# linSen.net
KiCad netlist of a schematic drawn in EAGLE
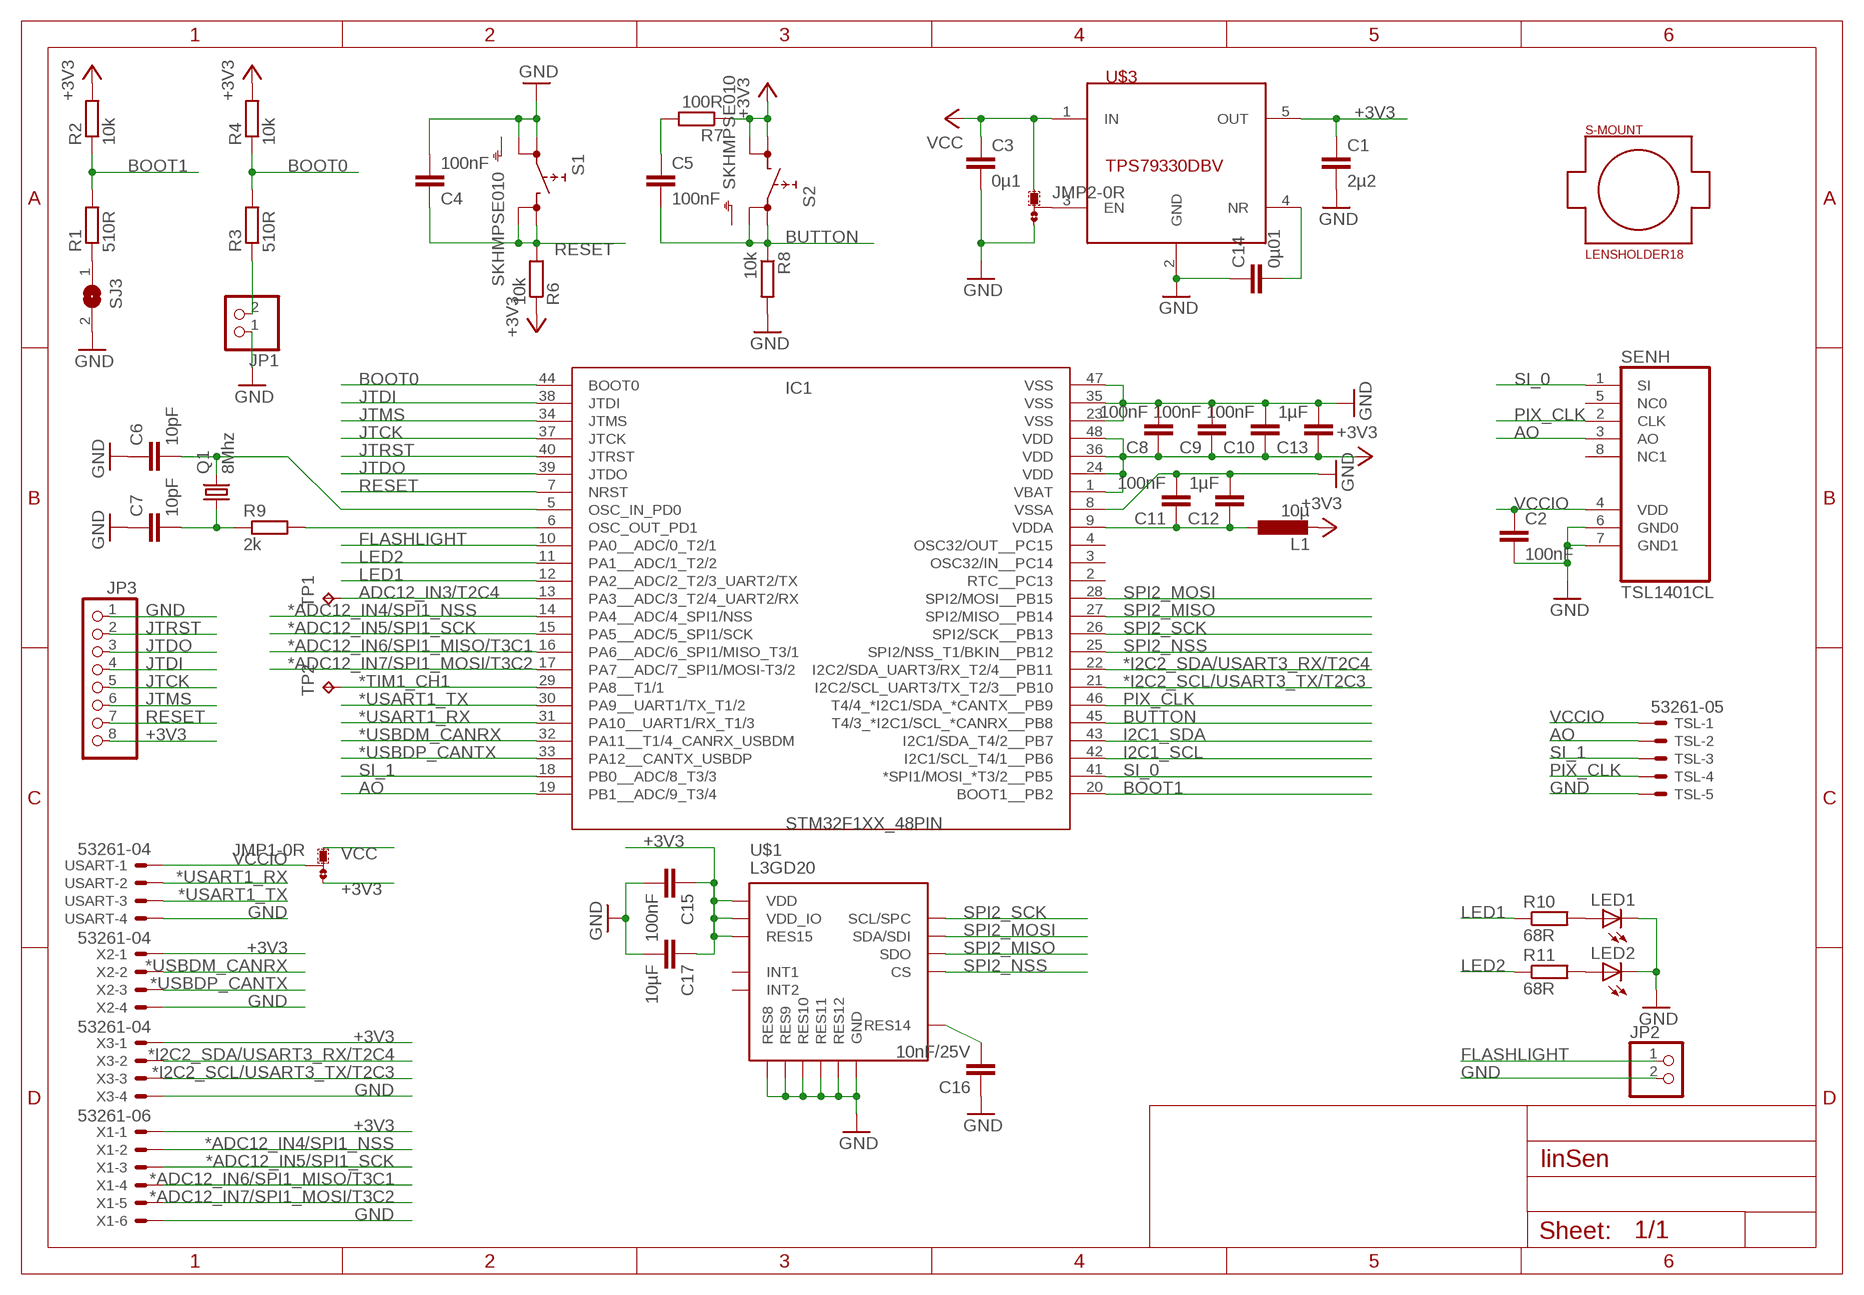
[diagram p0: schematic, sheet 1]

(export (version "E")
  (design (tool "Eeschema 10.0.6"))
  (components
    (comp (ref "C1")
      (value "2µ2")
      (footprint "eagle-import:C0805")
      (libsource (lib "eagle-import") (part "C-EUC0805"))
    )
    (comp (ref "C2")
      (value "100nF")
      (footprint "eagle-import:C0603")
      (libsource (lib "eagle-import") (part "C-EUC0603"))
    )
    (comp (ref "C3")
      (value "0µ1")
      (footprint "eagle-import:C0603")
      (libsource (lib "eagle-import") (part "C-EUC0603"))
    )
    (comp (ref "C4")
      (value "100nF")
      (footprint "eagle-import:C0603")
      (libsource (lib "eagle-import") (part "C-EUC0603"))
    )
    (comp (ref "C5")
      (value "100nF")
      (footprint "eagle-import:C0603")
      (libsource (lib "eagle-import") (part "C-EUC0603"))
    )
    (comp (ref "C6")
      (value "10pF")
      (footprint "eagle-import:C0603")
      (libsource (lib "eagle-import") (part "C-EUC0603"))
    )
    (comp (ref "C7")
      (value "10pF")
      (footprint "eagle-import:C0603")
      (libsource (lib "eagle-import") (part "C-EUC0603"))
    )
    (comp (ref "C8")
      (value "100nF")
      (footprint "eagle-import:C0603")
      (libsource (lib "eagle-import") (part "C-EUC0603"))
    )
    (comp (ref "C9")
      (value "100nF")
      (footprint "eagle-import:C0603")
      (libsource (lib "eagle-import") (part "C-EUC0603"))
    )
    (comp (ref "C10")
      (value "100nF")
      (footprint "eagle-import:C0603")
      (libsource (lib "eagle-import") (part "C-EUC0603"))
    )
    (comp (ref "C11")
      (value "100nF")
      (footprint "eagle-import:C0603")
      (libsource (lib "eagle-import") (part "C-EUC0603"))
    )
    (comp (ref "C12")
      (value "1µF")
      (footprint "eagle-import:C0603")
      (libsource (lib "eagle-import") (part "C-EUC0603"))
    )
    (comp (ref "C13")
      (value "1µF")
      (footprint "eagle-import:C0603")
      (libsource (lib "eagle-import") (part "C-EUC0603"))
    )
    (comp (ref "C14")
      (value "0µ01")
      (footprint "eagle-import:C0603")
      (libsource (lib "eagle-import") (part "C-EUC0603"))
    )
    (comp (ref "C15")
      (value "100nF")
      (footprint "eagle-import:C0603")
      (libsource (lib "eagle-import") (part "C-EUC0603"))
    )
    (comp (ref "C16")
      (value "10nF/25V")
      (footprint "eagle-import:C0603")
      (libsource (lib "eagle-import") (part "C-EUC0603"))
    )
    (comp (ref "C17")
      (value "10µF")
      (footprint "eagle-import:C0603")
      (libsource (lib "eagle-import") (part "C-EUC0603"))
    )
    (comp (ref "IC1")
      (value "STM32F1XX_48PIN")
      (footprint "eagle-import:LQFP48_PACKAGE")
      (libsource (lib "eagle-import") (part "STM32F1XX_48PIN"))
    )
    (comp (ref "JMP1")
      (value "0R-JUMPB")
      (footprint "eagle-import:B0R-JMP")
      (libsource (lib "eagle-import") (part "0R-JUMPB"))
    )
    (comp (ref "JMP2")
      (value "0R-JUMPB")
      (footprint "eagle-import:B0R-JMP")
      (libsource (lib "eagle-import") (part "0R-JUMPB"))
    )
    (comp (ref "JP1")
      (value "PINHD-1X2/90")
      (footprint "eagle-import:1X02_90")
      (libsource (lib "eagle-import") (part "PINHD-1X2/90"))
    )
    (comp (ref "JP2")
      (value "PINHD-1X2")
      (footprint "eagle-import:1X02")
      (libsource (lib "eagle-import") (part "PINHD-1X2"))
    )
    (comp (ref "JP3")
      (value "PINHD-1X8/SMD")
      (footprint "eagle-import:SMD-PAD-08")
      (libsource (lib "eagle-import") (part "PINHD-1X8/SMD"))
    )
    (comp (ref "L1")
      (value "10µ")
      (footprint "eagle-import:L2012C")
      (libsource (lib "eagle-import") (part "L-EUL2012C"))
    )
    (comp (ref "LED1")
      (value "LEDCHIPLED_0603")
      (footprint "eagle-import:CHIPLED_0603")
      (libsource (lib "eagle-import") (part "LEDCHIPLED_0603"))
    )
    (comp (ref "LED2")
      (value "LEDCHIPLED_0603")
      (footprint "eagle-import:CHIPLED_0603")
      (libsource (lib "eagle-import") (part "LEDCHIPLED_0603"))
    )
    (comp (ref "Q1")
      (value "8Mhz")
      (footprint "eagle-import:SM49")
      (libsource (lib "eagle-import") (part "CRYSTALSM49"))
    )
    (comp (ref "R1")
      (value "510R")
      (footprint "eagle-import:R0603")
      (libsource (lib "eagle-import") (part "R-EU_R0603"))
    )
    (comp (ref "R2")
      (value "10k")
      (footprint "eagle-import:R0603")
      (libsource (lib "eagle-import") (part "R-EU_R0603"))
    )
    (comp (ref "R3")
      (value "510R")
      (footprint "eagle-import:R0603")
      (libsource (lib "eagle-import") (part "R-EU_R0603"))
    )
    (comp (ref "R4")
      (value "10k")
      (footprint "eagle-import:R0603")
      (libsource (lib "eagle-import") (part "R-EU_R0603"))
    )
    (comp (ref "R6")
      (value "10k")
      (footprint "eagle-import:R0603")
      (libsource (lib "eagle-import") (part "R-EU_R0603"))
    )
    (comp (ref "R7")
      (value "100R")
      (footprint "eagle-import:R0603")
      (libsource (lib "eagle-import") (part "R-EU_R0603"))
    )
    (comp (ref "R8")
      (value "10k")
      (footprint "eagle-import:R0603")
      (libsource (lib "eagle-import") (part "R-EU_R0603"))
    )
    (comp (ref "R9")
      (value "2k")
      (footprint "eagle-import:R0603")
      (libsource (lib "eagle-import") (part "R-EU_R0603"))
    )
    (comp (ref "R10")
      (value "68R")
      (footprint "eagle-import:R0603")
      (libsource (lib "eagle-import") (part "R-EU_R0603"))
    )
    (comp (ref "R11")
      (value "68R")
      (footprint "eagle-import:R0603")
      (libsource (lib "eagle-import") (part "R-EU_R0603"))
    )
    (comp (ref "S-MOUNT")
      (value "LENSHOLDER18")
      (footprint "eagle-import:SMOUNT18")
      (libsource (lib "eagle-import") (part "LENSHOLDER18"))
    )
    (comp (ref "S1")
      (value "SKHMPSE010")
      (footprint "eagle-import:SKHMPXE010")
      (libsource (lib "eagle-import") (part "SKHMPE010S"))
    )
    (comp (ref "S2")
      (value "SKHMPSE010")
      (footprint "eagle-import:SKHMPXE010")
      (libsource (lib "eagle-import") (part "SKHMPE010S"))
    )
    (comp (ref "SENH")
      (value "TSL1401CL")
      (footprint "eagle-import:TSL1401CL")
      (libsource (lib "eagle-import") (part "TSL1401CL"))
    )
    (comp (ref "SJ3") (value "SJ") (footprint "eagle-import:SJ") (libsource (lib "eagle-import") (part "SJ")))
    (comp (ref "TP1")
      (value "TPB1,27")
      (footprint "eagle-import:B1,27")
      (libsource (lib "eagle-import") (part "TPB1,27"))
    )
    (comp (ref "TP2")
      (value "TPB1,27")
      (footprint "eagle-import:B1,27")
      (libsource (lib "eagle-import") (part "TPB1,27"))
    )
    (comp (ref "TSL")
      (value "53261-05")
      (footprint "eagle-import:53261-05")
      (fields (field (name "OC_FARNELL") "1433644"))
      (libsource (lib "eagle-import") (part "53?-05261"))
    )
    (comp (ref "U$1")
      (value "L3GD20")
      (footprint "eagle-import:LGA-16")
      (libsource (lib "eagle-import") (part "L3GD20"))
    )
    (comp (ref "U$3")
      (value "TPS79330DBV")
      (footprint "eagle-import:SOT23-5")
      (libsource (lib "eagle-import") (part "TPS793XXDBV"))
    )
    (comp (ref "USART")
      (value "53261-04")
      (footprint "eagle-import:53261-04")
      (libsource (lib "eagle-import") (part "53?-04261"))
    )
    (comp (ref "X1")
      (value "53261-06")
      (footprint "eagle-import:53261-06")
      (fields (field (name "OC_FARNELL") "1125375") (field (name "OC_NEWARK") "unknown"))
      (libsource (lib "eagle-import") (part "53?-06261"))
    )
    (comp (ref "X2")
      (value "53261-04")
      (footprint "eagle-import:53261-04")
      (libsource (lib "eagle-import") (part "53?-04261"))
    )
    (comp (ref "X3")
      (value "53261-04")
      (footprint "eagle-import:53261-04")
      (libsource (lib "eagle-import") (part "53?-04261"))
    )
  )
  (nets
    (net (code "1") (name "+3V3") (class "Default")
      (node (ref "C1") (pin "1") (pinfunction "1_1") (pintype "passive"))
      (node (ref "C10") (pin "1") (pinfunction "1_1") (pintype "passive"))
      (node (ref "C13") (pin "1") (pinfunction "1_1") (pintype "passive"))
      (node (ref "C15") (pin "1") (pinfunction "1_1") (pintype "passive"))
      (node (ref "C17") (pin "1") (pinfunction "1_1") (pintype "passive"))
      (node (ref "C8") (pin "1") (pinfunction "1_1") (pintype "passive"))
      (node (ref "C9") (pin "1") (pinfunction "1_1") (pintype "passive"))
      (node (ref "IC1") (pin "1") (pinfunction "VBAT_1") (pintype "passive"))
      (node (ref "IC1") (pin "24") (pinfunction "VDD_24") (pintype "power_in"))
      (node (ref "IC1") (pin "36") (pinfunction "VDD_36") (pintype "power_in"))
      (node (ref "IC1") (pin "48") (pinfunction "VDD_48") (pintype "power_in"))
      (node (ref "JMP1") (pin "3") (pinfunction "3_3") (pintype "passive"))
      (node (ref "JP3") (pin "8") (pinfunction "8_8") (pintype "passive"))
      (node (ref "L1") (pin "2") (pinfunction "2_2") (pintype "passive"))
      (node (ref "R2") (pin "2") (pinfunction "2_2") (pintype "passive"))
      (node (ref "R4") (pin "2") (pinfunction "2_2") (pintype "passive"))
      (node (ref "R6") (pin "1") (pinfunction "1_1") (pintype "passive"))
      (node (ref "R7") (pin "1") (pinfunction "1_1") (pintype "passive"))
      (node (ref "S2") (pin "3") (pinfunction "2.1_3") (pintype "passive"))
      (node (ref "S2") (pin "4") (pinfunction "2.2_4") (pintype "passive"))
      (node (ref "U$1") (pin "P$1") (pinfunction "VDD_IO_P$1") (pintype "power_in"))
      (node (ref "U$1") (pin "P$15") (pinfunction "RES15_P$15") (pintype "power_in"))
      (node (ref "U$1") (pin "P$16") (pinfunction "VDD_P$16") (pintype "power_in"))
      (node (ref "U$3") (pin "5") (pinfunction "OUT_5") (pintype "bidirectional"))
      (node (ref "X1") (pin "1") (pinfunction "S_1") (pintype "passive"))
      (node (ref "X2") (pin "1") (pinfunction "S_1") (pintype "passive"))
      (node (ref "X3") (pin "1") (pinfunction "S_1") (pintype "passive"))
    )
    (net (code "2") (name "/*ADC12_IN4{slash}SPI1_NSS") (class "Default")
      (node (ref "IC1") (pin "14") (pinfunction "PA4__ADC/4_SPI1/NSS_14") (pintype "bidirectional"))
      (node (ref "X1") (pin "2") (pinfunction "S_2") (pintype "passive"))
    )
    (net (code "3") (name "/*ADC12_IN5{slash}SPI1_SCK") (class "Default")
      (node (ref "IC1") (pin "15") (pinfunction "PA5__ADC/5_SPI1/SCK_15") (pintype "bidirectional"))
      (node (ref "X1") (pin "3") (pinfunction "S_3") (pintype "passive"))
    )
    (net (code "4") (name "/*ADC12_IN6{slash}SPI1_MISO{slash}T3C1") (class "Default")
      (node (ref "IC1") (pin "16") (pinfunction "PA6__ADC/6_SPI1/MISO_T3/1_16") (pintype "bidirectional"))
      (node (ref "X1") (pin "4") (pinfunction "S_4") (pintype "passive"))
    )
    (net (code "5") (name "/*ADC12_IN7{slash}SPI1_MOSI{slash}T3C2") (class "Default")
      (node (ref "IC1") (pin "17") (pinfunction "PA7__ADC/7_SPI1/MOSI-T3/2_17") (pintype "bidirectional"))
      (node (ref "X1") (pin "5") (pinfunction "S_5") (pintype "passive"))
    )
    (net (code "6") (name "/*I2C2_SCL{slash}USART3_TX{slash}T2C3") (class "Default")
      (node (ref "IC1") (pin "21") (pinfunction "I2C2/SCL_UART3/TX_T2/3__PB10_21") (pintype "bidirectional"))
      (node (ref "X3") (pin "3") (pinfunction "S_3") (pintype "passive"))
    )
    (net (code "7") (name "/*I2C2_SDA{slash}USART3_RX{slash}T2C4") (class "Default")
      (node (ref "IC1") (pin "22") (pinfunction "I2C2/SDA_UART3/RX_T2/4__PB11_22") (pintype "bidirectional"))
      (node (ref "X3") (pin "2") (pinfunction "S_2") (pintype "passive"))
    )
    (net (code "8") (name "/*TIM1_CH1") (class "Default")
      (node (ref "IC1") (pin "29") (pinfunction "PA8__T1/1_29") (pintype "bidirectional"))
      (node (ref "TP2") (pin "TP") (pinfunction "TP_TP") (pintype "input"))
    )
    (net (code "9") (name "/*USART1_RX") (class "Default")
      (node (ref "IC1") (pin "31") (pinfunction "PA10__UART1/RX_T1/3_31") (pintype "bidirectional"))
      (node (ref "USART") (pin "2") (pinfunction "S_2") (pintype "passive"))
    )
    (net (code "10") (name "/*USART1_TX") (class "Default")
      (node (ref "IC1") (pin "30") (pinfunction "PA9__UART1/TX_T1/2_30") (pintype "bidirectional"))
      (node (ref "USART") (pin "3") (pinfunction "S_3") (pintype "passive"))
    )
    (net (code "11") (name "/*USBDM_CANRX") (class "Default")
      (node (ref "IC1") (pin "32") (pinfunction "PA11__T1/4_CANRX_USBDM_32") (pintype "bidirectional"))
      (node (ref "X2") (pin "2") (pinfunction "S_2") (pintype "passive"))
    )
    (net (code "12") (name "/*USBDP_CANTX") (class "Default")
      (node (ref "IC1") (pin "33") (pinfunction "PA12__CANTX_USBDP_33") (pintype "bidirectional"))
      (node (ref "X2") (pin "3") (pinfunction "S_3") (pintype "passive"))
    )
    (net (code "13") (name "/ADC12_IN3{slash}T2C4") (class "Default")
      (node (ref "IC1") (pin "13") (pinfunction "PA3__ADC/3_T2/4_UART2/RX_13") (pintype "bidirectional"))
      (node (ref "TP1") (pin "TP") (pinfunction "TP_TP") (pintype "input"))
    )
    (net (code "14") (name "/AO") (class "Default")
      (node (ref "IC1") (pin "19") (pinfunction "PB1__ADC/9_T3/4_19") (pintype "bidirectional"))
      (node (ref "SENH") (pin "3") (pinfunction "AO_3") (pintype "output"))
      (node (ref "TSL") (pin "2") (pinfunction "S_2") (pintype "passive"))
    )
    (net (code "15") (name "/BOOT0") (class "Default")
      (node (ref "IC1") (pin "44") (pinfunction "BOOT0_44") (pintype "input"))
      (node (ref "R3") (pin "2") (pinfunction "2_2") (pintype "passive"))
      (node (ref "R4") (pin "1") (pinfunction "1_1") (pintype "passive"))
    )
    (net (code "16") (name "/BOOT1") (class "Default")
      (node (ref "IC1") (pin "20") (pinfunction "BOOT1__PB2_20") (pintype "bidirectional"))
      (node (ref "R1") (pin "2") (pinfunction "2_2") (pintype "passive"))
      (node (ref "R2") (pin "1") (pinfunction "1_1") (pintype "passive"))
    )
    (net (code "17") (name "/BUTTON") (class "Default")
      (node (ref "C5") (pin "2") (pinfunction "2_2") (pintype "passive"))
      (node (ref "IC1") (pin "45") (pinfunction "T4/3_*I2C1/SCL_*CANRX__PB8_45") (pintype "bidirectional"))
      (node (ref "R8") (pin "1") (pinfunction "1_1") (pintype "passive"))
      (node (ref "S2") (pin "1") (pinfunction "1.1_1") (pintype "passive"))
      (node (ref "S2") (pin "2") (pinfunction "1.2_2") (pintype "passive"))
    )
    (net (code "18") (name "/FLASHLIGHT") (class "Default")
      (node (ref "IC1") (pin "10") (pinfunction "PA0__ADC/0_T2/1_10") (pintype "bidirectional"))
      (node (ref "JP2") (pin "1") (pinfunction "1_1") (pintype "passive"))
    )
    (net (code "19") (name "/I2C1_SCL") (class "Default")
      (node (ref "IC1") (pin "42") (pinfunction "I2C1/SCL_T4/1__PB6_42") (pintype "bidirectional"))
    )
    (net (code "20") (name "/I2C1_SDA") (class "Default")
      (node (ref "IC1") (pin "43") (pinfunction "I2C1/SDA_T4/2__PB7_43") (pintype "bidirectional"))
    )
    (net (code "21") (name "/JTCK") (class "Default")
      (node (ref "IC1") (pin "37") (pinfunction "JTCK_37") (pintype "input"))
      (node (ref "JP3") (pin "5") (pinfunction "5_5") (pintype "passive"))
    )
    (net (code "22") (name "/JTDI") (class "Default")
      (node (ref "IC1") (pin "38") (pinfunction "JTDI_38") (pintype "input"))
      (node (ref "JP3") (pin "4") (pinfunction "4_4") (pintype "passive"))
    )
    (net (code "23") (name "/JTDO") (class "Default")
      (node (ref "IC1") (pin "39") (pinfunction "JTDO_39") (pintype "output"))
      (node (ref "JP3") (pin "3") (pinfunction "3_3") (pintype "passive"))
    )
    (net (code "24") (name "/JTMS") (class "Default")
      (node (ref "IC1") (pin "34") (pinfunction "JTMS_34") (pintype "input"))
      (node (ref "JP3") (pin "6") (pinfunction "6_6") (pintype "passive"))
    )
    (net (code "25") (name "/JTRST") (class "Default")
      (node (ref "IC1") (pin "40") (pinfunction "JTRST_40") (pintype "input"))
      (node (ref "JP3") (pin "2") (pinfunction "2_2") (pintype "passive"))
    )
    (net (code "26") (name "/LED1") (class "Default")
      (node (ref "IC1") (pin "12") (pinfunction "PA2__ADC/2_T2/3_UART2/TX_12") (pintype "bidirectional"))
      (node (ref "R10") (pin "1") (pinfunction "1_1") (pintype "passive"))
    )
    (net (code "27") (name "/LED2") (class "Default")
      (node (ref "IC1") (pin "11") (pinfunction "PA1__ADC/1_T2/2_11") (pintype "bidirectional"))
      (node (ref "R11") (pin "1") (pinfunction "1_1") (pintype "passive"))
    )
    (net (code "28") (name "/PIX_CLK") (class "Default")
      (node (ref "IC1") (pin "46") (pinfunction "T4/4_*I2C1/SDA_*CANTX__PB9_46") (pintype "bidirectional"))
      (node (ref "SENH") (pin "2") (pinfunction "CLK_2") (pintype "input"))
      (node (ref "TSL") (pin "4") (pinfunction "S_4") (pintype "passive"))
    )
    (net (code "29") (name "/RESET") (class "Default")
      (node (ref "C4") (pin "1") (pinfunction "1_1") (pintype "passive"))
      (node (ref "IC1") (pin "7") (pinfunction "NRST_7") (pintype "input"))
      (node (ref "JP3") (pin "7") (pinfunction "7_7") (pintype "passive"))
      (node (ref "R6") (pin "2") (pinfunction "2_2") (pintype "passive"))
      (node (ref "S1") (pin "3") (pinfunction "2.1_3") (pintype "passive"))
      (node (ref "S1") (pin "4") (pinfunction "2.2_4") (pintype "passive"))
    )
    (net (code "30") (name "/SI_0") (class "Default")
      (node (ref "IC1") (pin "41") (pinfunction "*SPI1/MOSI_*T3/2__PB5_41") (pintype "bidirectional"))
      (node (ref "SENH") (pin "1") (pinfunction "SI_1") (pintype "input"))
    )
    (net (code "31") (name "/SI_1") (class "Default")
      (node (ref "IC1") (pin "18") (pinfunction "PB0__ADC/8_T3/3_18") (pintype "bidirectional"))
      (node (ref "TSL") (pin "3") (pinfunction "S_3") (pintype "passive"))
    )
    (net (code "32") (name "/SPI2_MISO") (class "Default")
      (node (ref "IC1") (pin "27") (pinfunction "SPI2/MISO__PB14_27") (pintype "bidirectional"))
      (node (ref "U$1") (pin "P$4") (pinfunction "SDO_P$4") (pintype "bidirectional"))
    )
    (net (code "33") (name "/SPI2_MOSI") (class "Default")
      (node (ref "IC1") (pin "28") (pinfunction "SPI2/MOSI__PB15_28") (pintype "bidirectional"))
      (node (ref "U$1") (pin "P$3") (pinfunction "SDA/SDI_P$3") (pintype "bidirectional"))
    )
    (net (code "34") (name "/SPI2_NSS") (class "Default")
      (node (ref "IC1") (pin "25") (pinfunction "SPI2/NSS_T1/BKIN__PB12_25") (pintype "bidirectional"))
      (node (ref "U$1") (pin "P$5") (pinfunction "CS_P$5") (pintype "input"))
    )
    (net (code "35") (name "/SPI2_SCK") (class "Default")
      (node (ref "IC1") (pin "26") (pinfunction "SPI2/SCK__PB13_26") (pintype "bidirectional"))
      (node (ref "U$1") (pin "P$2") (pinfunction "SCL/SPC_P$2") (pintype "input"))
    )
    (net (code "36") (name "/VCCIO") (class "Default")
      (node (ref "C2") (pin "1") (pinfunction "1_1") (pintype "passive"))
      (node (ref "JMP1") (pin "2") (pinfunction "2_2") (pintype "passive"))
      (node (ref "SENH") (pin "4") (pinfunction "VDD_4") (pintype "power_in"))
      (node (ref "TSL") (pin "1") (pinfunction "S_1") (pintype "passive"))
      (node (ref "USART") (pin "1") (pinfunction "S_1") (pintype "passive"))
    )
    (net (code "37") (name "GND") (class "Default")
      (node (ref "C1") (pin "2") (pinfunction "2_2") (pintype "passive"))
      (node (ref "C10") (pin "2") (pinfunction "2_2") (pintype "passive"))
      (node (ref "C11") (pin "2") (pinfunction "2_2") (pintype "passive"))
      (node (ref "C12") (pin "2") (pinfunction "2_2") (pintype "passive"))
      (node (ref "C13") (pin "2") (pinfunction "2_2") (pintype "passive"))
      (node (ref "C14") (pin "1") (pinfunction "1_1") (pintype "passive"))
      (node (ref "C15") (pin "2") (pinfunction "2_2") (pintype "passive"))
      (node (ref "C16") (pin "1") (pinfunction "1_1") (pintype "passive"))
      (node (ref "C17") (pin "2") (pinfunction "2_2") (pintype "passive"))
      (node (ref "C2") (pin "2") (pinfunction "2_2") (pintype "passive"))
      (node (ref "C3") (pin "2") (pinfunction "2_2") (pintype "passive"))
      (node (ref "C4") (pin "2") (pinfunction "2_2") (pintype "passive"))
      (node (ref "C6") (pin "1") (pinfunction "1_1") (pintype "passive"))
      (node (ref "C7") (pin "1") (pinfunction "1_1") (pintype "passive"))
      (node (ref "C8") (pin "2") (pinfunction "2_2") (pintype "passive"))
      (node (ref "C9") (pin "2") (pinfunction "2_2") (pintype "passive"))
      (node (ref "IC1") (pin "23") (pinfunction "VSS_23") (pintype "power_in"))
      (node (ref "IC1") (pin "35") (pinfunction "VSS_35") (pintype "power_in"))
      (node (ref "IC1") (pin "47") (pinfunction "VSS_47") (pintype "power_in"))
      (node (ref "IC1") (pin "8") (pinfunction "VSSA_8") (pintype "power_in"))
      (node (ref "JMP2") (pin "3") (pinfunction "3_3") (pintype "passive"))
      (node (ref "JP1") (pin "1") (pinfunction "1_1") (pintype "passive"))
      (node (ref "JP2") (pin "2") (pinfunction "2_2") (pintype "passive"))
      (node (ref "JP3") (pin "1") (pinfunction "1_1") (pintype "passive"))
      (node (ref "LED1") (pin "C") (pinfunction "C_C") (pintype "passive"))
      (node (ref "LED2") (pin "C") (pinfunction "C_C") (pintype "passive"))
      (node (ref "R8") (pin "2") (pinfunction "2_2") (pintype "passive"))
      (node (ref "S1") (pin "1") (pinfunction "1.1_1") (pintype "passive"))
      (node (ref "S1") (pin "2") (pinfunction "1.2_2") (pintype "passive"))
      (node (ref "SENH") (pin "6") (pinfunction "GND0_6") (pintype "power_in"))
      (node (ref "SENH") (pin "7") (pinfunction "GND1_7") (pintype "power_in"))
      (node (ref "SJ3") (pin "2") (pinfunction "2_2") (pintype "passive"))
      (node (ref "TSL") (pin "5") (pinfunction "S_5") (pintype "passive"))
      (node (ref "U$1") (pin "P$10") (pinfunction "RES10_P$10") (pintype "power_in"))
      (node (ref "U$1") (pin "P$11") (pinfunction "RES11_P$11") (pintype "power_in"))
      (node (ref "U$1") (pin "P$12") (pinfunction "RES12_P$12") (pintype "power_in"))
      (node (ref "U$1") (pin "P$13") (pinfunction "GND_P$13") (pintype "power_in"))
      (node (ref "U$1") (pin "P$8") (pinfunction "RES8_P$8") (pintype "power_in"))
      (node (ref "U$1") (pin "P$9") (pinfunction "RES9_P$9") (pintype "power_in"))
      (node (ref "U$3") (pin "2") (pinfunction "GND_2") (pintype "bidirectional"))
      (node (ref "USART") (pin "4") (pinfunction "S_4") (pintype "passive"))
      (node (ref "X1") (pin "6") (pinfunction "S_6") (pintype "passive"))
      (node (ref "X2") (pin "4") (pinfunction "S_4") (pintype "passive"))
      (node (ref "X3") (pin "4") (pinfunction "S_4") (pintype "passive"))
    )
    (net (code "38") (name "Net-(C5-Pad1)") (class "Default")
      (node (ref "C5") (pin "1") (pinfunction "1_1") (pintype "passive"))
      (node (ref "R7") (pin "2") (pinfunction "2_2") (pintype "passive"))
    )
    (net (code "39") (name "Net-(C7-Pad2)") (class "Default")
      (node (ref "C7") (pin "2") (pinfunction "2_2") (pintype "passive"))
      (node (ref "Q1") (pin "1") (pinfunction "1_1") (pintype "passive"))
      (node (ref "R9") (pin "1") (pinfunction "1_1") (pintype "passive"))
    )
    (net (code "40") (name "Net-(IC1-OSC_IN_PD0)") (class "Default")
      (node (ref "C6") (pin "2") (pinfunction "2_2") (pintype "passive"))
      (node (ref "IC1") (pin "5") (pinfunction "OSC_IN_PD0_5") (pintype "bidirectional"))
      (node (ref "Q1") (pin "2") (pinfunction "2_2") (pintype "passive"))
    )
    (net (code "41") (name "Net-(IC1-OSC_OUT_PD1)") (class "Default")
      (node (ref "IC1") (pin "6") (pinfunction "OSC_OUT_PD1_6") (pintype "bidirectional"))
      (node (ref "R9") (pin "2") (pinfunction "2_2") (pintype "passive"))
    )
    (net (code "42") (name "Net-(IC1-VDDA)") (class "Default")
      (node (ref "C11") (pin "1") (pinfunction "1_1") (pintype "passive"))
      (node (ref "C12") (pin "1") (pinfunction "1_1") (pintype "passive"))
      (node (ref "IC1") (pin "9") (pinfunction "VDDA_9") (pintype "power_in"))
      (node (ref "L1") (pin "1") (pinfunction "1_1") (pintype "passive"))
    )
    (net (code "43") (name "Net-(JP1-Pad2)") (class "Default")
      (node (ref "JP1") (pin "2") (pinfunction "2_2") (pintype "passive"))
      (node (ref "R3") (pin "1") (pinfunction "1_1") (pintype "passive"))
    )
    (net (code "44") (name "Net-(LED1-PadA)") (class "Default")
      (node (ref "LED1") (pin "A") (pinfunction "A_A") (pintype "passive"))
      (node (ref "R10") (pin "2") (pinfunction "2_2") (pintype "passive"))
    )
    (net (code "45") (name "Net-(LED2-PadA)") (class "Default")
      (node (ref "LED2") (pin "A") (pinfunction "A_A") (pintype "passive"))
      (node (ref "R11") (pin "2") (pinfunction "2_2") (pintype "passive"))
    )
    (net (code "46") (name "Net-(R1-Pad1)") (class "Default")
      (node (ref "R1") (pin "1") (pinfunction "1_1") (pintype "passive"))
      (node (ref "SJ3") (pin "1") (pinfunction "1_1") (pintype "passive"))
    )
    (net (code "47") (name "Net-(U$1-RES14)") (class "Default")
      (node (ref "C16") (pin "2") (pinfunction "2_2") (pintype "passive"))
      (node (ref "U$1") (pin "P$14") (pinfunction "RES14_P$14") (pintype "power_in"))
    )
    (net (code "48") (name "Net-(U$3-EN)") (class "Default")
      (node (ref "JMP2") (pin "2") (pinfunction "2_2") (pintype "passive"))
      (node (ref "U$3") (pin "3") (pinfunction "EN_3") (pintype "bidirectional"))
    )
    (net (code "49") (name "Net-(U$3-NR)") (class "Default")
      (node (ref "C14") (pin "2") (pinfunction "2_2") (pintype "passive"))
      (node (ref "U$3") (pin "4") (pinfunction "NR_4") (pintype "bidirectional"))
    )
    (net (code "50") (name "VCC") (class "Default")
      (node (ref "C3") (pin "1") (pinfunction "1_1") (pintype "passive"))
      (node (ref "JMP1") (pin "1") (pinfunction "1_1") (pintype "passive"))
      (node (ref "JMP2") (pin "1") (pinfunction "1_1") (pintype "passive"))
      (node (ref "U$3") (pin "1") (pinfunction "IN_1") (pintype "bidirectional"))
    )
    (net (code "51") (name "unconnected-(IC1-OSC32{slash}IN__PC14-Pad3)") (class "Default")
      (node (ref "IC1") (pin "3") (pinfunction "OSC32/IN__PC14_3") (pintype "bidirectional"))
    )
    (net (code "52") (name "unconnected-(IC1-OSC32{slash}OUT__PC15-Pad4)") (class "Default")
      (node (ref "IC1") (pin "4") (pinfunction "OSC32/OUT__PC15_4") (pintype "bidirectional"))
    )
    (net (code "53") (name "unconnected-(IC1-RTC__PC13-Pad2)") (class "Default")
      (node (ref "IC1") (pin "2") (pinfunction "RTC__PC13_2") (pintype "bidirectional"))
    )
    (net (code "54") (name "unconnected-(S1-SH-Pad5)") (class "Default")
      (node (ref "S1") (pin "5") (pinfunction "SH_5") (pintype "passive"))
    )
    (net (code "55") (name "unconnected-(S2-SH-Pad5)") (class "Default")
      (node (ref "S2") (pin "5") (pinfunction "SH_5") (pintype "passive"))
    )
    (net (code "56") (name "unconnected-(SENH-NC0-Pad5)") (class "Default")
      (node (ref "SENH") (pin "5") (pinfunction "NC0_5") (pintype "no_connect"))
    )
    (net (code "57") (name "unconnected-(SENH-NC1-Pad8)") (class "Default")
      (node (ref "SENH") (pin "8") (pinfunction "NC1_8") (pintype "no_connect"))
    )
    (net (code "58") (name "unconnected-(U$1-INT1-PadP$7)") (class "Default")
      (node (ref "U$1") (pin "P$7") (pinfunction "INT1_P$7") (pintype "output"))
    )
    (net (code "59") (name "unconnected-(U$1-INT2-PadP$6)") (class "Default")
      (node (ref "U$1") (pin "P$6") (pinfunction "INT2_P$6") (pintype "output"))
    )
  )
)
